# 02_-_Interfaces.net
KiCad netlist of a schematic drawn in Altium Designer
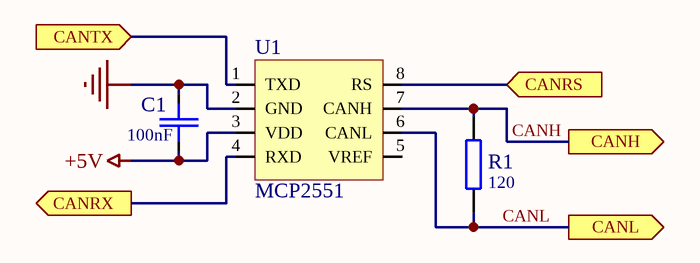
[diagram p0: 02 - Interfaces.SchDoc]

(export (version "E")
  (design (tool "Eeschema 10.0.6"))
  (components
    (comp (ref "C1")
      (value "100nF")
      (footprint "CAP: 0805")
      (description "SMD-0805")
      (libsource (lib "RCL_SMD_Integrated_Library") (part "C-0805"))
    )
    (comp (ref "R1")
      (value "120")
      (footprint "RES: 0805")
      (description "SMD 0805 0.1W 5% 150V")
      (libsource (lib "RCL_SMD_Integrated_Library") (part "R-0805"))
    )
    (comp (ref "U1")
      (value "MCP2551")
      (footprint "SOIC-8N")
      (libsource (lib "stm32_Integrated_Library") (part "MCP2551"))
    )
  )
  (nets
    (net (code "1") (name "+5V") (class "Default")
      (node (ref "C1") (pin "1") (pinfunction "1_1") (pintype "passive"))
      (node (ref "U1") (pin "3") (pinfunction "VDD_3") (pintype "passive"))
    )
    (net (code "2") (name "/CANH") (class "Default")
      (node (ref "R1") (pin "2") (pinfunction "2_2") (pintype "passive"))
      (node (ref "U1") (pin "7") (pinfunction "CANH_7") (pintype "passive"))
    )
    (net (code "3") (name "/CANL") (class "Default")
      (node (ref "R1") (pin "1") (pinfunction "1_1") (pintype "passive"))
      (node (ref "U1") (pin "6") (pinfunction "CANL_6") (pintype "passive"))
    )
    (net (code "4") (name "/CANRS") (class "Default")
      (node (ref "U1") (pin "8") (pinfunction "RS_8") (pintype "passive"))
    )
    (net (code "5") (name "/CANRX") (class "Default")
      (node (ref "U1") (pin "4") (pinfunction "RXD_4") (pintype "passive"))
    )
    (net (code "6") (name "/CANTX") (class "Default")
      (node (ref "U1") (pin "1") (pinfunction "TXD_1") (pintype "passive"))
    )
    (net (code "7") (name "GND") (class "Default")
      (node (ref "C1") (pin "2") (pinfunction "2_2") (pintype "passive"))
      (node (ref "U1") (pin "2") (pinfunction "GND_2") (pintype "passive"))
    )
    (net (code "8") (name "unconnected-(U1-VREF-Pad5)") (class "Default")
      (node (ref "U1") (pin "5") (pinfunction "VREF_5") (pintype "passive"))
    )
  )
)
